# TPS_v1.net
KiCad netlist of a schematic drawn in EAGLE
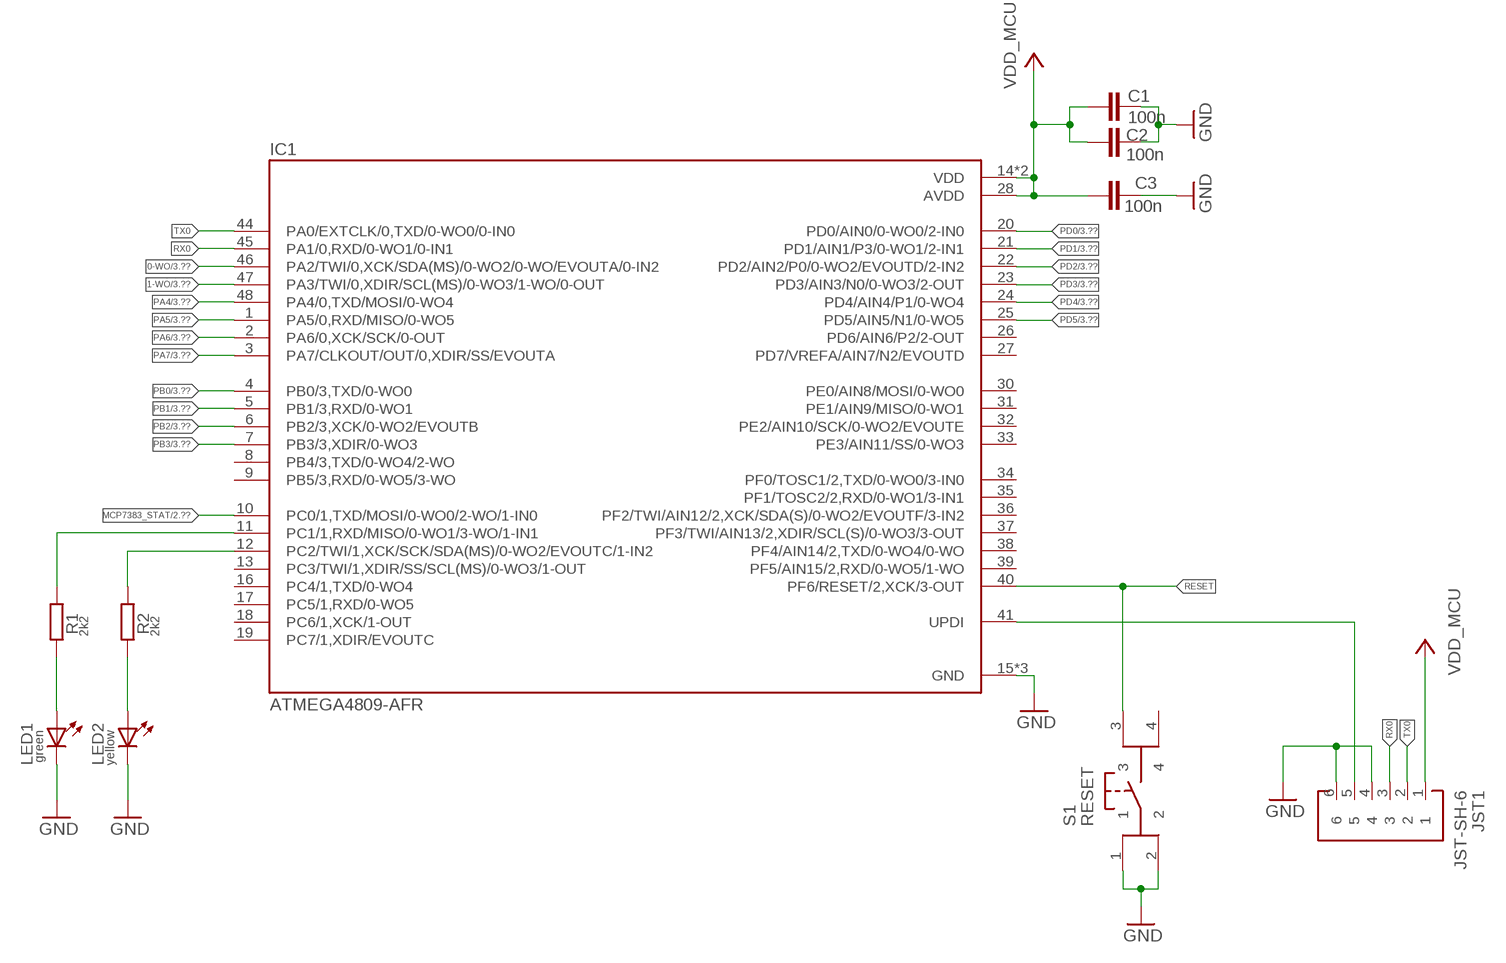
[diagram p0: schematic, sheet 1]
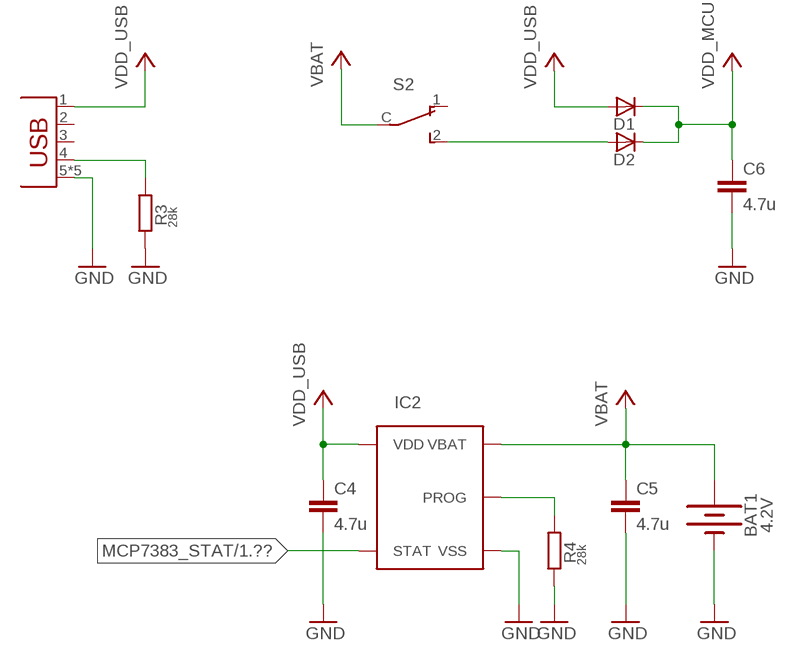
[diagram p1: schematic, sheet 2]
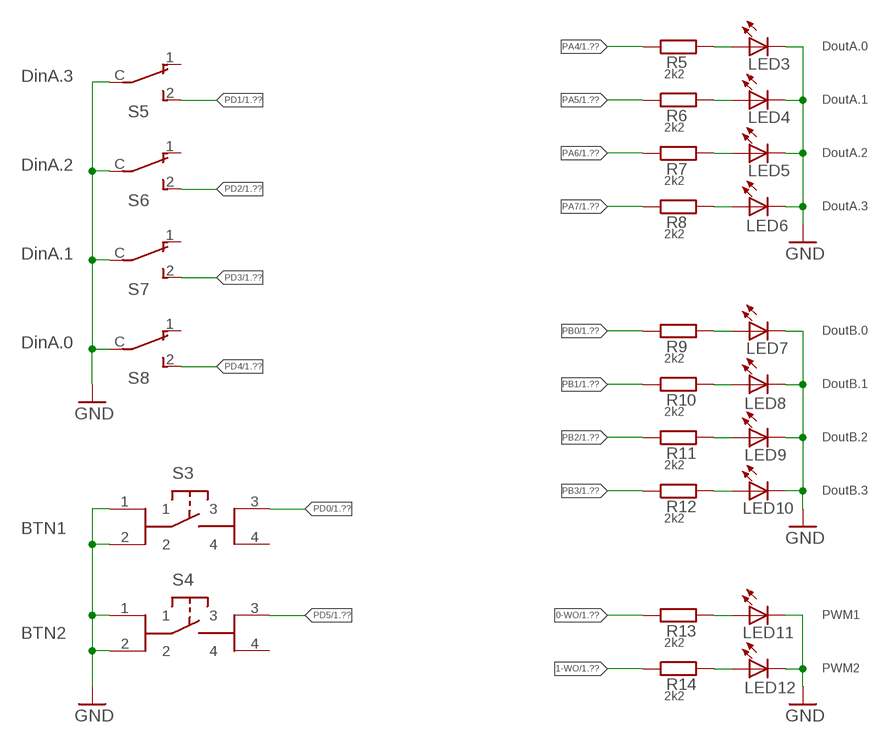
[diagram p2: schematic, sheet 3]

(export (version "E")
  (design (tool "Eeschema 10.0.6"))
  (components
    (comp (ref "LED3")
      (value "DoutA.0")
      (footprint "eagle-import:LED_1206")
      (libsource (lib "eagle-import") (part "LED"))
    )
    (comp (ref "LED4")
      (value "DoutA.1")
      (footprint "eagle-import:LED_1206")
      (libsource (lib "eagle-import") (part "LED"))
    )
    (comp (ref "LED5")
      (value "DoutA.2")
      (footprint "eagle-import:LED_1206")
      (libsource (lib "eagle-import") (part "LED"))
    )
    (comp (ref "LED6")
      (value "DoutA.3")
      (footprint "eagle-import:LED_1206")
      (libsource (lib "eagle-import") (part "LED"))
    )
    (comp (ref "LED7")
      (value "DoutB.0")
      (footprint "eagle-import:LED_1206")
      (libsource (lib "eagle-import") (part "LED"))
    )
    (comp (ref "LED8")
      (value "DoutB.1")
      (footprint "eagle-import:LED_1206")
      (libsource (lib "eagle-import") (part "LED"))
    )
    (comp (ref "LED9")
      (value "DoutB.2")
      (footprint "eagle-import:LED_1206")
      (libsource (lib "eagle-import") (part "LED"))
    )
    (comp (ref "LED10")
      (value "DoutB.3")
      (footprint "eagle-import:LED_1206")
      (libsource (lib "eagle-import") (part "LED"))
    )
    (comp (ref "LED11")
      (value "PWM1")
      (footprint "eagle-import:LED_1206")
      (libsource (lib "eagle-import") (part "LED"))
    )
    (comp (ref "LED12")
      (value "PWM2")
      (footprint "eagle-import:LED_1206")
      (libsource (lib "eagle-import") (part "LED"))
    )
    (comp (ref "R5")
      (value "2k2")
      (footprint "eagle-import:R0603")
      (libsource (lib "eagle-import") (part "RESISTOR"))
    )
    (comp (ref "R6")
      (value "2k2")
      (footprint "eagle-import:R0603")
      (libsource (lib "eagle-import") (part "RESISTOR"))
    )
    (comp (ref "R7")
      (value "2k2")
      (footprint "eagle-import:R0603")
      (libsource (lib "eagle-import") (part "RESISTOR"))
    )
    (comp (ref "R8")
      (value "2k2")
      (footprint "eagle-import:R0603")
      (libsource (lib "eagle-import") (part "RESISTOR"))
    )
    (comp (ref "R9")
      (value "2k2")
      (footprint "eagle-import:R0603")
      (libsource (lib "eagle-import") (part "RESISTOR"))
    )
    (comp (ref "R10")
      (value "2k2")
      (footprint "eagle-import:R0603")
      (libsource (lib "eagle-import") (part "RESISTOR"))
    )
    (comp (ref "R11")
      (value "2k2")
      (footprint "eagle-import:R0603")
      (libsource (lib "eagle-import") (part "RESISTOR"))
    )
    (comp (ref "R12")
      (value "2k2")
      (footprint "eagle-import:R0603")
      (libsource (lib "eagle-import") (part "RESISTOR"))
    )
    (comp (ref "R13")
      (value "2k2")
      (footprint "eagle-import:R0603")
      (libsource (lib "eagle-import") (part "RESISTOR"))
    )
    (comp (ref "R14")
      (value "2k2")
      (footprint "eagle-import:R0603")
      (libsource (lib "eagle-import") (part "RESISTOR"))
    )
    (comp (ref "S3")
      (value "BTN1")
      (footprint "eagle-import:B3FS-1012")
      (fields
        (field (name "MANUFACTURER_PART_NUMBER") "B3FS-1012")
        (field (name "RS_PART_NUMBER") "6821260P")
      )
      (libsource (lib "eagle-import") (part "BUTTON"))
    )
    (comp (ref "S4")
      (value "BTN2")
      (footprint "eagle-import:B3FS-1012")
      (fields
        (field (name "MANUFACTURER_PART_NUMBER") "B3FS-1012")
        (field (name "RS_PART_NUMBER") "6821260P")
      )
      (libsource (lib "eagle-import") (part "BUTTON"))
    )
    (comp (ref "S5")
      (value "DinA.3")
      (footprint "eagle-import:ESP40XX")
      (libsource (lib "eagle-import") (part "SWITCH"))
    )
    (comp (ref "S6")
      (value "DinA.2")
      (footprint "eagle-import:ESP40XX")
      (libsource (lib "eagle-import") (part "SWITCH"))
    )
    (comp (ref "S7")
      (value "DinA.1")
      (footprint "eagle-import:ESP40XX")
      (libsource (lib "eagle-import") (part "SWITCH"))
    )
    (comp (ref "S8")
      (value "DinA.0")
      (footprint "eagle-import:ESP40XX")
      (libsource (lib "eagle-import") (part "SWITCH"))
    )
    (comp (ref "BAT1")
      (value "4.2V")
      (footprint "eagle-import:CELL-CLIP_PAD_20MM")
      (libsource (lib "eagle-import") (part "BATTERYPAD"))
    )
    (comp (ref "C4")
      (value "4.7u")
      (footprint "eagle-import:C0603")
      (libsource (lib "eagle-import") (part "CAPACITORC0603"))
    )
    (comp (ref "C5")
      (value "4.7u")
      (footprint "eagle-import:C0603")
      (libsource (lib "eagle-import") (part "CAPACITORC0603"))
    )
    (comp (ref "C6")
      (value "4.7u")
      (footprint "eagle-import:C0603")
      (libsource (lib "eagle-import") (part "CAPACITORC0603"))
    )
    (comp (ref "D1")
      (value "DIODE")
      (footprint "eagle-import:MBR0530T1")
      (libsource (lib "eagle-import") (part "DIODE"))
    )
    (comp (ref "D2")
      (value "DIODE")
      (footprint "eagle-import:MBR0530T1")
      (libsource (lib "eagle-import") (part "DIODE"))
    )
    (comp (ref "IC2")
      (value "MCP7383")
      (footprint "eagle-import:SOT23-5")
      (libsource (lib "eagle-import") (part "MCP7383"))
    )
    (comp (ref "R3")
      (value "28k")
      (footprint "eagle-import:R0603")
      (libsource (lib "eagle-import") (part "RESISTOR"))
    )
    (comp (ref "R4")
      (value "28k")
      (footprint "eagle-import:R0603")
      (libsource (lib "eagle-import") (part "RESISTOR"))
    )
    (comp (ref "S2")
      (value "SWITCH")
      (footprint "eagle-import:ESP40XX")
      (libsource (lib "eagle-import") (part "SWITCH"))
    )
    (comp (ref "USB1")
      (value "USB")
      (footprint "eagle-import:629105136821")
      (libsource (lib "eagle-import") (part "USB"))
    )
    (comp (ref "C1")
      (value "100n")
      (footprint "eagle-import:C0603")
      (libsource (lib "eagle-import") (part "CAPACITORC0603"))
    )
    (comp (ref "C2")
      (value "100n")
      (footprint "eagle-import:C0603")
      (libsource (lib "eagle-import") (part "CAPACITORC0603"))
    )
    (comp (ref "C3")
      (value "100n")
      (footprint "eagle-import:C0603")
      (libsource (lib "eagle-import") (part "CAPACITORC0603"))
    )
    (comp (ref "IC1")
      (value "ATMEGA4809-AFR")
      (footprint "eagle-import:QFP50P900X900X120-48N")
      (fields (field (name "MF") "Microchip"))
      (libsource (lib "eagle-import") (part "ATMEGA4809-AFR"))
    )
    (comp (ref "JST1")
      (value "JST-SH-6")
      (footprint "eagle-import:JST-SH-6")
      (fields
        (field (name "MANUFACTURER_PART_NUMBER") "SM06B-SRSS-TB (LF)(SN)")
        (field (name "RS_PART_NUMBER") "5468827")
      )
      (libsource (lib "eagle-import") (part "JST-SH-6"))
    )
    (comp (ref "LED1")
      (value "green")
      (footprint "eagle-import:LED_0603")
      (libsource (lib "eagle-import") (part "LED0603"))
    )
    (comp (ref "LED2")
      (value "yellow")
      (footprint "eagle-import:LED_0603")
      (libsource (lib "eagle-import") (part "LED0603"))
    )
    (comp (ref "R1")
      (value "2k2")
      (footprint "eagle-import:R0603")
      (libsource (lib "eagle-import") (part "RESISTOR"))
    )
    (comp (ref "R2")
      (value "2k2")
      (footprint "eagle-import:R0603")
      (libsource (lib "eagle-import") (part "RESISTOR"))
    )
    (comp (ref "S1")
      (value "RESET")
      (footprint "eagle-import:B3FS-1012")
      (fields
        (field (name "MANUFACTURER_PART_NUMBER") "B3FS-1012")
        (field (name "RS_PART_NUMBER") "6821260P")
      )
      (libsource (lib "eagle-import") (part "BUTTON"))
    )
  )
  (nets
    (net (code "1") (name "0-WO") (class "Default")
      (node (ref "IC1") (pin "46") (pinfunction "PA2/TWI/0,XCK/SDA(MS)/0-WO2/0-WO/EVOUTA/0-IN2_46") (pintype "bidirectional"))
      (node (ref "R13") (pin "1") (pinfunction "1_1") (pintype "passive"))
    )
    (net (code "2") (name "1-WO") (class "Default")
      (node (ref "IC1") (pin "47") (pinfunction "PA3/TWI/0,XDIR/SCL(MS)/0-WO3/1-WO/0-OUT_47") (pintype "bidirectional"))
      (node (ref "R14") (pin "1") (pinfunction "1_1") (pintype "passive"))
    )
    (net (code "3") (name "GND") (class "Default")
      (node (ref "BAT1") (pin "-") (pinfunction "-_-") (pintype "power_in"))
      (node (ref "C1") (pin "2") (pinfunction "2_2") (pintype "passive"))
      (node (ref "C2") (pin "2") (pinfunction "2_2") (pintype "passive"))
      (node (ref "C3") (pin "2") (pinfunction "2_2") (pintype "passive"))
      (node (ref "C4") (pin "2") (pinfunction "2_2") (pintype "passive"))
      (node (ref "C5") (pin "2") (pinfunction "2_2") (pintype "passive"))
      (node (ref "C6") (pin "2") (pinfunction "2_2") (pintype "passive"))
      (node (ref "IC1") (pin "15") (pinfunction "GND_15") (pintype "power_in"))
      (node (ref "IC1") (pin "29") (pinfunction "GND_29") (pintype "power_in"))
      (node (ref "IC1") (pin "43") (pinfunction "GND_43") (pintype "power_in"))
      (node (ref "IC2") (pin "2") (pinfunction "VSS_2") (pintype "bidirectional"))
      (node (ref "JST1") (pin "4") (pinfunction "4_4") (pintype "bidirectional"))
      (node (ref "JST1") (pin "6") (pinfunction "6_6") (pintype "bidirectional"))
      (node (ref "LED1") (pin "C") (pinfunction "C_C") (pintype "passive"))
      (node (ref "LED10") (pin "C") (pinfunction "C_C") (pintype "passive"))
      (node (ref "LED11") (pin "C") (pinfunction "C_C") (pintype "passive"))
      (node (ref "LED12") (pin "C") (pinfunction "C_C") (pintype "passive"))
      (node (ref "LED2") (pin "C") (pinfunction "C_C") (pintype "passive"))
      (node (ref "LED3") (pin "C") (pinfunction "C_C") (pintype "passive"))
      (node (ref "LED4") (pin "C") (pinfunction "C_C") (pintype "passive"))
      (node (ref "LED5") (pin "C") (pinfunction "C_C") (pintype "passive"))
      (node (ref "LED6") (pin "C") (pinfunction "C_C") (pintype "passive"))
      (node (ref "LED7") (pin "C") (pinfunction "C_C") (pintype "passive"))
      (node (ref "LED8") (pin "C") (pinfunction "C_C") (pintype "passive"))
      (node (ref "LED9") (pin "C") (pinfunction "C_C") (pintype "passive"))
      (node (ref "R3") (pin "1") (pinfunction "1_1") (pintype "passive"))
      (node (ref "R4") (pin "1") (pinfunction "1_1") (pintype "passive"))
      (node (ref "S1") (pin "1") (pinfunction "1_1") (pintype "bidirectional"))
      (node (ref "S1") (pin "2") (pinfunction "2_2") (pintype "bidirectional"))
      (node (ref "S3") (pin "1") (pinfunction "1_1") (pintype "bidirectional"))
      (node (ref "S3") (pin "2") (pinfunction "2_2") (pintype "bidirectional"))
      (node (ref "S4") (pin "1") (pinfunction "1_1") (pintype "bidirectional"))
      (node (ref "S4") (pin "2") (pinfunction "2_2") (pintype "bidirectional"))
      (node (ref "S5") (pin "C") (pinfunction "C_C") (pintype "passive"))
      (node (ref "S6") (pin "C") (pinfunction "C_C") (pintype "passive"))
      (node (ref "S7") (pin "C") (pinfunction "C_C") (pintype "passive"))
      (node (ref "S8") (pin "C") (pinfunction "C_C") (pintype "passive"))
      (node (ref "USB1") (pin "5") (pinfunction "GND_5") (pintype "bidirectional"))
      (node (ref "USB1") (pin "Z1") (pinfunction "GND_Z1") (pintype "bidirectional"))
      (node (ref "USB1") (pin "Z2") (pinfunction "GND_Z2") (pintype "bidirectional"))
      (node (ref "USB1") (pin "Z3") (pinfunction "GND_Z3") (pintype "bidirectional"))
      (node (ref "USB1") (pin "Z4") (pinfunction "GND_Z4") (pintype "bidirectional"))
    )
    (net (code "4") (name "MCP7383_STAT") (class "Default")
      (node (ref "IC1") (pin "10") (pinfunction "PC0/1,TXD/MOSI/0-WO0/2-WO/1-IN0_10") (pintype "bidirectional"))
      (node (ref "IC2") (pin "1") (pinfunction "STAT_1") (pintype "bidirectional"))
    )
    (net (code "5") (name "Net-(D2-A)") (class "Default")
      (node (ref "D2") (pin "P$1") (pinfunction "A_P$1") (pintype "passive"))
      (node (ref "S2") (pin "2") (pinfunction "2_2") (pintype "passive"))
    )
    (net (code "6") (name "Net-(IC1-PC1{slash}1,RXD{slash}MISO{slash}0-WO1{slash}3-WO{slash}1-IN1)") (class "Default")
      (node (ref "IC1") (pin "11") (pinfunction "PC1/1,RXD/MISO/0-WO1/3-WO/1-IN1_11") (pintype "bidirectional"))
      (node (ref "R1") (pin "2") (pinfunction "2_2") (pintype "passive"))
    )
    (net (code "7") (name "Net-(IC1-PC2{slash}TWI{slash}1,XCK{slash}SCK{slash}SDA(MS){slash}0-WO2{slash}EVOUTC{slash}1-IN2)") (class "Default")
      (node (ref "IC1") (pin "12") (pinfunction "PC2/TWI/1,XCK/SCK/SDA(MS)/0-WO2/EVOUTC/1-IN2_12") (pintype "bidirectional"))
      (node (ref "R2") (pin "2") (pinfunction "2_2") (pintype "passive"))
    )
    (net (code "8") (name "Net-(IC1-UPDI)") (class "Default")
      (node (ref "IC1") (pin "41") (pinfunction "UPDI_41") (pintype "bidirectional"))
      (node (ref "JST1") (pin "5") (pinfunction "5_5") (pintype "bidirectional"))
    )
    (net (code "9") (name "Net-(IC2-PROG)") (class "Default")
      (node (ref "IC2") (pin "5") (pinfunction "PROG_5") (pintype "bidirectional"))
      (node (ref "R4") (pin "2") (pinfunction "2_2") (pintype "passive"))
    )
    (net (code "10") (name "Net-(LED1-PadA)") (class "Default")
      (node (ref "LED1") (pin "A") (pinfunction "A_A") (pintype "passive"))
      (node (ref "R1") (pin "1") (pinfunction "1_1") (pintype "passive"))
    )
    (net (code "11") (name "Net-(LED2-PadA)") (class "Default")
      (node (ref "LED2") (pin "A") (pinfunction "A_A") (pintype "passive"))
      (node (ref "R2") (pin "1") (pinfunction "1_1") (pintype "passive"))
    )
    (net (code "12") (name "Net-(LED3-PadA)") (class "Default")
      (node (ref "LED3") (pin "A") (pinfunction "A_A") (pintype "passive"))
      (node (ref "R5") (pin "2") (pinfunction "2_2") (pintype "passive"))
    )
    (net (code "13") (name "Net-(LED4-PadA)") (class "Default")
      (node (ref "LED4") (pin "A") (pinfunction "A_A") (pintype "passive"))
      (node (ref "R6") (pin "2") (pinfunction "2_2") (pintype "passive"))
    )
    (net (code "14") (name "Net-(LED5-PadA)") (class "Default")
      (node (ref "LED5") (pin "A") (pinfunction "A_A") (pintype "passive"))
      (node (ref "R7") (pin "2") (pinfunction "2_2") (pintype "passive"))
    )
    (net (code "15") (name "Net-(LED6-PadA)") (class "Default")
      (node (ref "LED6") (pin "A") (pinfunction "A_A") (pintype "passive"))
      (node (ref "R8") (pin "2") (pinfunction "2_2") (pintype "passive"))
    )
    (net (code "16") (name "Net-(LED7-PadA)") (class "Default")
      (node (ref "LED7") (pin "A") (pinfunction "A_A") (pintype "passive"))
      (node (ref "R9") (pin "2") (pinfunction "2_2") (pintype "passive"))
    )
    (net (code "17") (name "Net-(LED8-PadA)") (class "Default")
      (node (ref "LED8") (pin "A") (pinfunction "A_A") (pintype "passive"))
      (node (ref "R10") (pin "2") (pinfunction "2_2") (pintype "passive"))
    )
    (net (code "18") (name "Net-(LED9-PadA)") (class "Default")
      (node (ref "LED9") (pin "A") (pinfunction "A_A") (pintype "passive"))
      (node (ref "R11") (pin "2") (pinfunction "2_2") (pintype "passive"))
    )
    (net (code "19") (name "Net-(LED10-PadA)") (class "Default")
      (node (ref "LED10") (pin "A") (pinfunction "A_A") (pintype "passive"))
      (node (ref "R12") (pin "2") (pinfunction "2_2") (pintype "passive"))
    )
    (net (code "20") (name "Net-(LED11-PadA)") (class "Default")
      (node (ref "LED11") (pin "A") (pinfunction "A_A") (pintype "passive"))
      (node (ref "R13") (pin "2") (pinfunction "2_2") (pintype "passive"))
    )
    (net (code "21") (name "Net-(LED12-PadA)") (class "Default")
      (node (ref "LED12") (pin "A") (pinfunction "A_A") (pintype "passive"))
      (node (ref "R14") (pin "2") (pinfunction "2_2") (pintype "passive"))
    )
    (net (code "22") (name "Net-(USB1-USBID)") (class "Default")
      (node (ref "R3") (pin "2") (pinfunction "2_2") (pintype "passive"))
      (node (ref "USB1") (pin "4") (pinfunction "USBID_4") (pintype "bidirectional"))
    )
    (net (code "23") (name "PA4") (class "Default")
      (node (ref "IC1") (pin "48") (pinfunction "PA4/0,TXD/MOSI/0-WO4_48") (pintype "bidirectional"))
      (node (ref "R5") (pin "1") (pinfunction "1_1") (pintype "passive"))
    )
    (net (code "24") (name "PA5") (class "Default")
      (node (ref "IC1") (pin "1") (pinfunction "PA5/0,RXD/MISO/0-WO5_1") (pintype "bidirectional"))
      (node (ref "R6") (pin "1") (pinfunction "1_1") (pintype "passive"))
    )
    (net (code "25") (name "PA6") (class "Default")
      (node (ref "IC1") (pin "2") (pinfunction "PA6/0,XCK/SCK/0-OUT_2") (pintype "bidirectional"))
      (node (ref "R7") (pin "1") (pinfunction "1_1") (pintype "passive"))
    )
    (net (code "26") (name "PA7") (class "Default")
      (node (ref "IC1") (pin "3") (pinfunction "PA7/CLKOUT/OUT/0,XDIR/SS/EVOUTA_3") (pintype "bidirectional"))
      (node (ref "R8") (pin "1") (pinfunction "1_1") (pintype "passive"))
    )
    (net (code "27") (name "PB0") (class "Default")
      (node (ref "IC1") (pin "4") (pinfunction "PB0/3,TXD/0-WO0_4") (pintype "bidirectional"))
      (node (ref "R9") (pin "1") (pinfunction "1_1") (pintype "passive"))
    )
    (net (code "28") (name "PB1") (class "Default")
      (node (ref "IC1") (pin "5") (pinfunction "PB1/3,RXD/0-WO1_5") (pintype "bidirectional"))
      (node (ref "R10") (pin "1") (pinfunction "1_1") (pintype "passive"))
    )
    (net (code "29") (name "PB2") (class "Default")
      (node (ref "IC1") (pin "6") (pinfunction "PB2/3,XCK/0-WO2/EVOUTB_6") (pintype "bidirectional"))
      (node (ref "R11") (pin "1") (pinfunction "1_1") (pintype "passive"))
    )
    (net (code "30") (name "PB3") (class "Default")
      (node (ref "IC1") (pin "7") (pinfunction "PB3/3,XDIR/0-WO3_7") (pintype "bidirectional"))
      (node (ref "R12") (pin "1") (pinfunction "1_1") (pintype "passive"))
    )
    (net (code "31") (name "PD0") (class "Default")
      (node (ref "IC1") (pin "20") (pinfunction "PD0/AIN0/0-WO0/2-IN0_20") (pintype "bidirectional"))
      (node (ref "S3") (pin "3") (pinfunction "3_3") (pintype "bidirectional"))
    )
    (net (code "32") (name "PD1") (class "Default")
      (node (ref "IC1") (pin "21") (pinfunction "PD1/AIN1/P3/0-WO1/2-IN1_21") (pintype "bidirectional"))
      (node (ref "S5") (pin "2") (pinfunction "2_2") (pintype "passive"))
    )
    (net (code "33") (name "PD2") (class "Default")
      (node (ref "IC1") (pin "22") (pinfunction "PD2/AIN2/P0/0-WO2/EVOUTD/2-IN2_22") (pintype "bidirectional"))
      (node (ref "S6") (pin "2") (pinfunction "2_2") (pintype "passive"))
    )
    (net (code "34") (name "PD3") (class "Default")
      (node (ref "IC1") (pin "23") (pinfunction "PD3/AIN3/N0/0-WO3/2-OUT_23") (pintype "bidirectional"))
      (node (ref "S7") (pin "2") (pinfunction "2_2") (pintype "passive"))
    )
    (net (code "35") (name "PD4") (class "Default")
      (node (ref "IC1") (pin "24") (pinfunction "PD4/AIN4/P1/0-WO4_24") (pintype "bidirectional"))
      (node (ref "S8") (pin "2") (pinfunction "2_2") (pintype "passive"))
    )
    (net (code "36") (name "PD5") (class "Default")
      (node (ref "IC1") (pin "25") (pinfunction "PD5/AIN5/N1/0-WO5_25") (pintype "bidirectional"))
      (node (ref "S4") (pin "3") (pinfunction "3_3") (pintype "bidirectional"))
    )
    (net (code "37") (name "RESET") (class "Default")
      (node (ref "IC1") (pin "40") (pinfunction "PF6/RESET/2,XCK/3-OUT_40") (pintype "bidirectional"))
      (node (ref "S1") (pin "3") (pinfunction "3_3") (pintype "bidirectional"))
    )
    (net (code "38") (name "RX0") (class "Default")
      (node (ref "IC1") (pin "45") (pinfunction "PA1/0,RXD/0-WO1/0-IN1_45") (pintype "bidirectional"))
      (node (ref "JST1") (pin "3") (pinfunction "3_3") (pintype "bidirectional"))
    )
    (net (code "39") (name "TX0") (class "Default")
      (node (ref "IC1") (pin "44") (pinfunction "PA0/EXTCLK/0,TXD/0-WO0/0-IN0_44") (pintype "bidirectional"))
      (node (ref "JST1") (pin "2") (pinfunction "2_2") (pintype "bidirectional"))
    )
    (net (code "40") (name "VBAT") (class "Default")
      (node (ref "BAT1") (pin "+1") (pinfunction "+_+1") (pintype "power_in"))
      (node (ref "BAT1") (pin "+2") (pinfunction "+_+2") (pintype "power_in"))
      (node (ref "C5") (pin "1") (pinfunction "1_1") (pintype "passive"))
      (node (ref "IC2") (pin "3") (pinfunction "VBAT_3") (pintype "bidirectional"))
      (node (ref "S2") (pin "C") (pinfunction "C_C") (pintype "passive"))
    )
    (net (code "41") (name "VDD_MCU") (class "Default")
      (node (ref "C1") (pin "1") (pinfunction "1_1") (pintype "passive"))
      (node (ref "C2") (pin "1") (pinfunction "1_1") (pintype "passive"))
      (node (ref "C3") (pin "1") (pinfunction "1_1") (pintype "passive"))
      (node (ref "C6") (pin "1") (pinfunction "1_1") (pintype "passive"))
      (node (ref "D1") (pin "P$2") (pinfunction "C_P$2") (pintype "passive"))
      (node (ref "D2") (pin "P$2") (pinfunction "C_P$2") (pintype "passive"))
      (node (ref "IC1") (pin "14") (pinfunction "VDD_14") (pintype "power_in"))
      (node (ref "IC1") (pin "28") (pinfunction "AVDD_28") (pintype "power_in"))
      (node (ref "IC1") (pin "42") (pinfunction "VDD_42") (pintype "power_in"))
      (node (ref "JST1") (pin "1") (pinfunction "1_1") (pintype "bidirectional"))
    )
    (net (code "42") (name "VDD_USB") (class "Default")
      (node (ref "C4") (pin "1") (pinfunction "1_1") (pintype "passive"))
      (node (ref "D1") (pin "P$1") (pinfunction "A_P$1") (pintype "passive"))
      (node (ref "IC2") (pin "4") (pinfunction "VDD_4") (pintype "bidirectional"))
      (node (ref "USB1") (pin "1") (pinfunction "VBUS_1") (pintype "bidirectional"))
    )
    (net (code "43") (name "unconnected-(IC1-PB4{slash}3,TXD{slash}0-WO4{slash}2-WO-Pad8)") (class "Default")
      (node (ref "IC1") (pin "8") (pinfunction "PB4/3,TXD/0-WO4/2-WO_8") (pintype "bidirectional"))
    )
    (net (code "44") (name "unconnected-(IC1-PB5{slash}3,RXD{slash}0-WO5{slash}3-WO-Pad9)") (class "Default")
      (node (ref "IC1") (pin "9") (pinfunction "PB5/3,RXD/0-WO5/3-WO_9") (pintype "bidirectional"))
    )
    (net (code "45") (name "unconnected-(IC1-PC3{slash}TWI{slash}1,XDIR{slash}SS{slash}SCL(MS){slash}0-WO3{slash}1-OUT-Pad13)") (class "Default")
      (node (ref "IC1") (pin "13") (pinfunction "PC3/TWI/1,XDIR/SS/SCL(MS)/0-WO3/1-OUT_13") (pintype "bidirectional"))
    )
    (net (code "46") (name "unconnected-(IC1-PC4{slash}1,TXD{slash}0-WO4-Pad16)") (class "Default")
      (node (ref "IC1") (pin "16") (pinfunction "PC4/1,TXD/0-WO4_16") (pintype "bidirectional"))
    )
    (net (code "47") (name "unconnected-(IC1-PC5{slash}1,RXD{slash}0-WO5-Pad17)") (class "Default")
      (node (ref "IC1") (pin "17") (pinfunction "PC5/1,RXD/0-WO5_17") (pintype "bidirectional"))
    )
    (net (code "48") (name "unconnected-(IC1-PC6{slash}1,XCK{slash}1-OUT-Pad18)") (class "Default")
      (node (ref "IC1") (pin "18") (pinfunction "PC6/1,XCK/1-OUT_18") (pintype "bidirectional"))
    )
    (net (code "49") (name "unconnected-(IC1-PC7{slash}1,XDIR{slash}EVOUTC-Pad19)") (class "Default")
      (node (ref "IC1") (pin "19") (pinfunction "PC7/1,XDIR/EVOUTC_19") (pintype "bidirectional"))
    )
    (net (code "50") (name "unconnected-(IC1-PD6{slash}AIN6{slash}P2{slash}2-OUT-Pad26)") (class "Default")
      (node (ref "IC1") (pin "26") (pinfunction "PD6/AIN6/P2/2-OUT_26") (pintype "bidirectional"))
    )
    (net (code "51") (name "unconnected-(IC1-PD7{slash}VREFA{slash}AIN7{slash}N2{slash}EVOUTD-Pad27)") (class "Default")
      (node (ref "IC1") (pin "27") (pinfunction "PD7/VREFA/AIN7/N2/EVOUTD_27") (pintype "bidirectional"))
    )
    (net (code "52") (name "unconnected-(IC1-PE0{slash}AIN8{slash}MOSI{slash}0-WO0-Pad30)") (class "Default")
      (node (ref "IC1") (pin "30") (pinfunction "PE0/AIN8/MOSI/0-WO0_30") (pintype "bidirectional"))
    )
    (net (code "53") (name "unconnected-(IC1-PE1{slash}AIN9{slash}MISO{slash}0-WO1-Pad31)") (class "Default")
      (node (ref "IC1") (pin "31") (pinfunction "PE1/AIN9/MISO/0-WO1_31") (pintype "bidirectional"))
    )
    (net (code "54") (name "unconnected-(IC1-PE2{slash}AIN10{slash}SCK{slash}0-WO2{slash}EVOUTE-Pad32)") (class "Default")
      (node (ref "IC1") (pin "32") (pinfunction "PE2/AIN10/SCK/0-WO2/EVOUTE_32") (pintype "bidirectional"))
    )
    (net (code "55") (name "unconnected-(IC1-PE3{slash}AIN11{slash}SS{slash}0-WO3-Pad33)") (class "Default")
      (node (ref "IC1") (pin "33") (pinfunction "PE3/AIN11/SS/0-WO3_33") (pintype "bidirectional"))
    )
    (net (code "56") (name "unconnected-(IC1-PF0{slash}TOSC1{slash}2,TXD{slash}0-WO0{slash}3-IN0-Pad34)") (class "Default")
      (node (ref "IC1") (pin "34") (pinfunction "PF0/TOSC1/2,TXD/0-WO0/3-IN0_34") (pintype "bidirectional"))
    )
    (net (code "57") (name "unconnected-(IC1-PF1{slash}TOSC2{slash}2,RXD{slash}0-WO1{slash}3-IN1-Pad35)") (class "Default")
      (node (ref "IC1") (pin "35") (pinfunction "PF1/TOSC2/2,RXD/0-WO1/3-IN1_35") (pintype "bidirectional"))
    )
    (net (code "58") (name "unconnected-(IC1-PF2{slash}TWI{slash}AIN12{slash}2,XCK{slash}SDA(S){slash}0-WO2{slash}EVOUTF{slash}3-IN2-Pad36)") (class "Default")
      (node (ref "IC1") (pin "36") (pinfunction "PF2/TWI/AIN12/2,XCK/SDA(S)/0-WO2/EVOUTF/3-IN2_36") (pintype "bidirectional"))
    )
    (net (code "59") (name "unconnected-(IC1-PF3{slash}TWI{slash}AIN13{slash}2,XDIR{slash}SCL(S){slash}0-WO3{slash}3-OUT-Pad37)") (class "Default")
      (node (ref "IC1") (pin "37") (pinfunction "PF3/TWI/AIN13/2,XDIR/SCL(S)/0-WO3/3-OUT_37") (pintype "bidirectional"))
    )
    (net (code "60") (name "unconnected-(IC1-PF4{slash}AIN14{slash}2,TXD{slash}0-WO4{slash}0-WO-Pad38)") (class "Default")
      (node (ref "IC1") (pin "38") (pinfunction "PF4/AIN14/2,TXD/0-WO4/0-WO_38") (pintype "bidirectional"))
    )
    (net (code "61") (name "unconnected-(IC1-PF5{slash}AIN15{slash}2,RXD{slash}0-WO5{slash}1-WO-Pad39)") (class "Default")
      (node (ref "IC1") (pin "39") (pinfunction "PF5/AIN15/2,RXD/0-WO5/1-WO_39") (pintype "bidirectional"))
    )
    (net (code "62") (name "unconnected-(S1-Pad4)") (class "Default")
      (node (ref "S1") (pin "4") (pinfunction "4_4") (pintype "bidirectional"))
    )
    (net (code "63") (name "unconnected-(S2-Pad1)") (class "Default")
      (node (ref "S2") (pin "1") (pinfunction "1_1") (pintype "passive"))
    )
    (net (code "64") (name "unconnected-(S3-Pad4)") (class "Default")
      (node (ref "S3") (pin "4") (pinfunction "4_4") (pintype "bidirectional"))
    )
    (net (code "65") (name "unconnected-(S4-Pad4)") (class "Default")
      (node (ref "S4") (pin "4") (pinfunction "4_4") (pintype "bidirectional"))
    )
    (net (code "66") (name "unconnected-(S5-Pad1)") (class "Default")
      (node (ref "S5") (pin "1") (pinfunction "1_1") (pintype "passive"))
    )
    (net (code "67") (name "unconnected-(S6-Pad1)") (class "Default")
      (node (ref "S6") (pin "1") (pinfunction "1_1") (pintype "passive"))
    )
    (net (code "68") (name "unconnected-(S7-Pad1)") (class "Default")
      (node (ref "S7") (pin "1") (pinfunction "1_1") (pintype "passive"))
    )
    (net (code "69") (name "unconnected-(S8-Pad1)") (class "Default")
      (node (ref "S8") (pin "1") (pinfunction "1_1") (pintype "passive"))
    )
    (net (code "70") (name "unconnected-(USB1-D+-Pad3)") (class "Default")
      (node (ref "USB1") (pin "3") (pinfunction "D+_3") (pintype "bidirectional"))
    )
    (net (code "71") (name "unconnected-(USB1-D--Pad2)") (class "Default")
      (node (ref "USB1") (pin "2") (pinfunction "D-_2") (pintype "bidirectional"))
    )
  )
)
